# supply.net
KiCad netlist of a schematic drawn in EAGLE
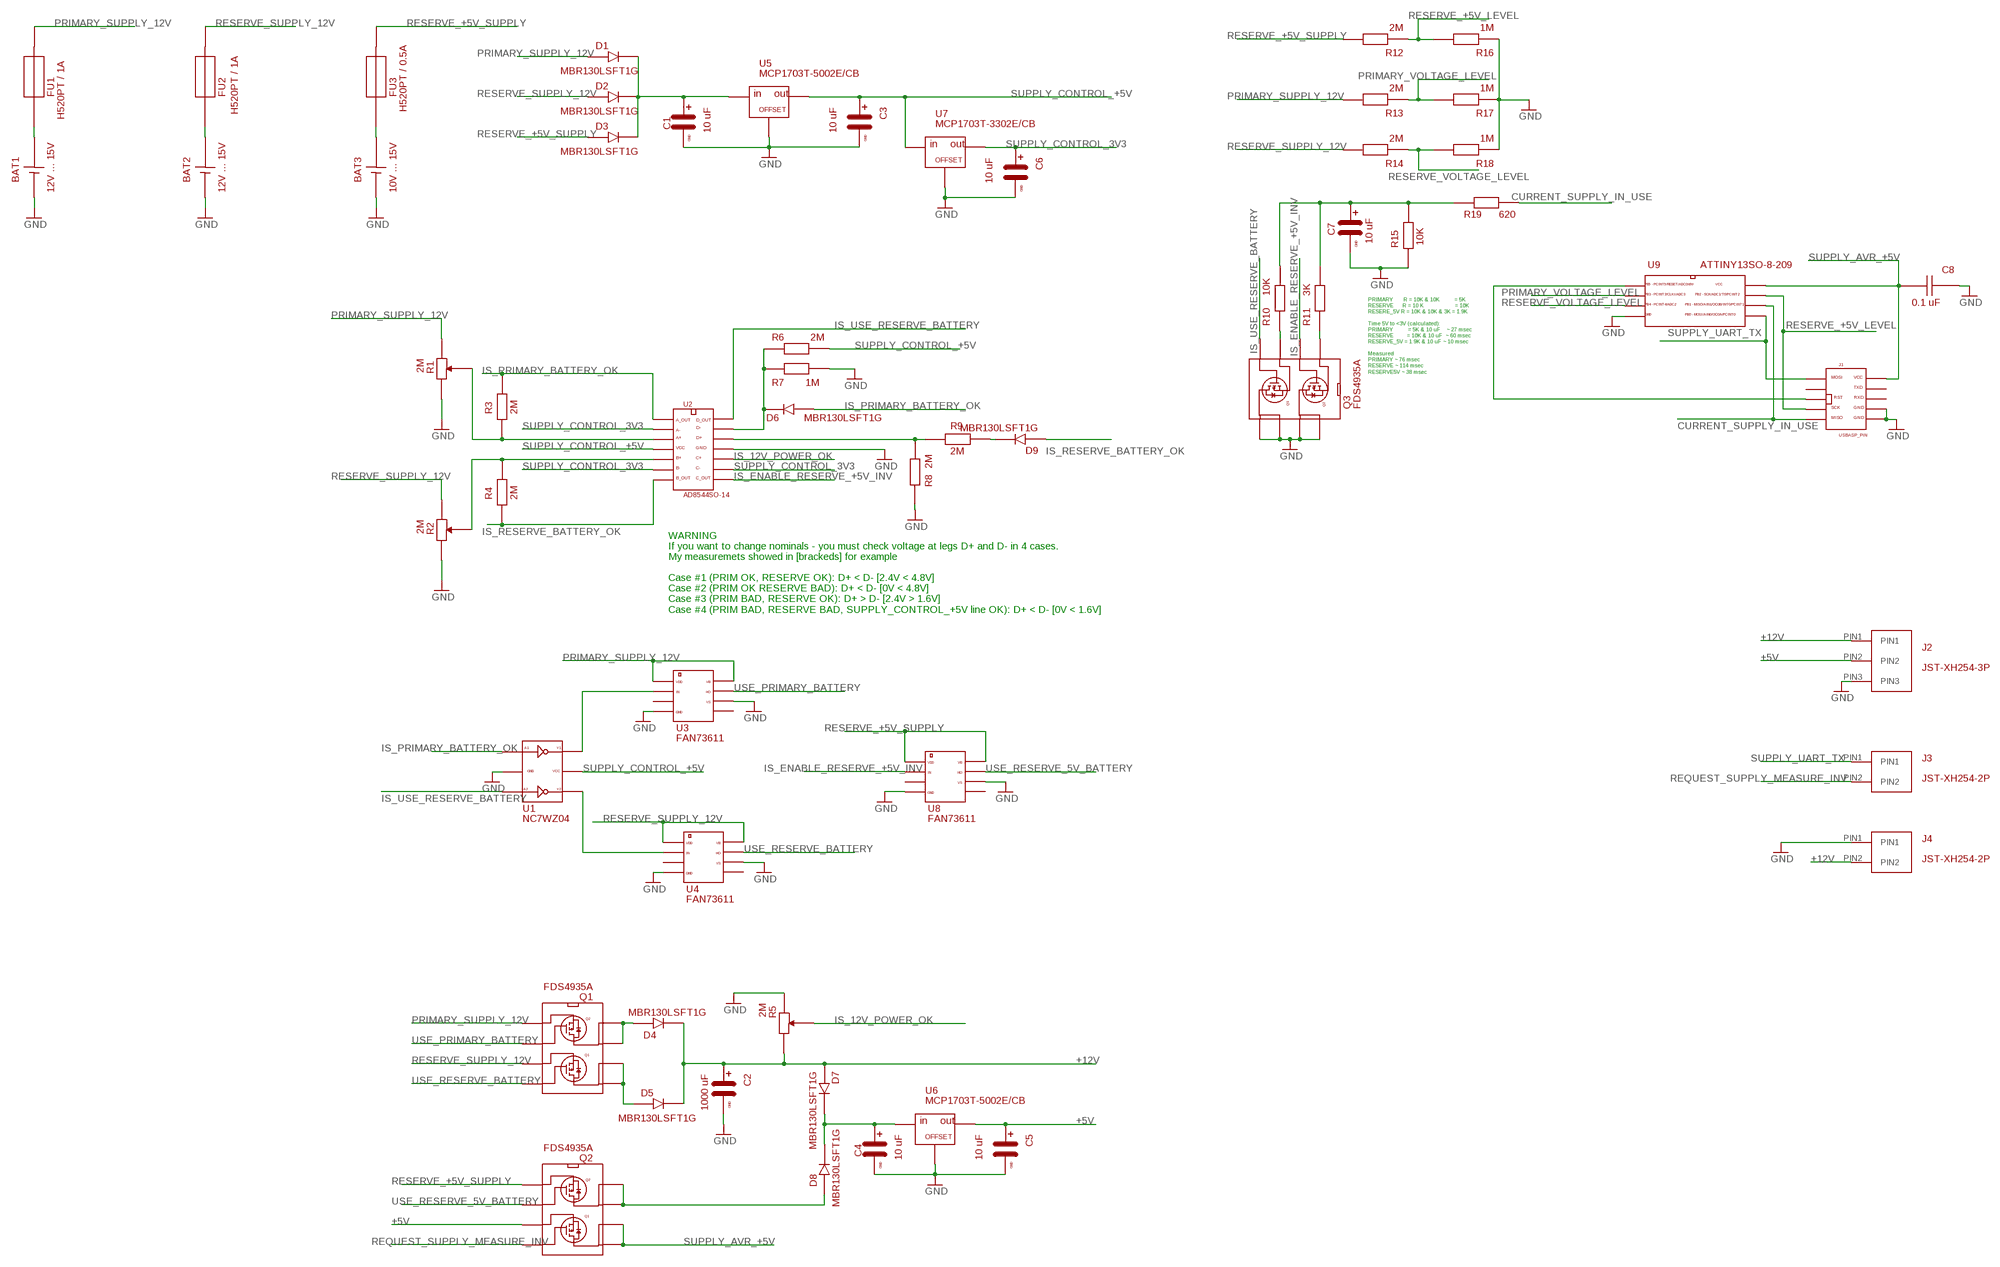
[diagram p0: schematic, sheet 1]

(export (version "E")
  (design (tool "Eeschema 10.0.6"))
  (components
    (comp (ref "BAT1")
      (value "12V ... 15V")
      (footprint "eagle-import:BATTERY")
      (libsource (lib "eagle-import") (part "BATTERY"))
    )
    (comp (ref "BAT2")
      (value "12V ... 15V")
      (footprint "eagle-import:BATTERY")
      (libsource (lib "eagle-import") (part "BATTERY"))
    )
    (comp (ref "BAT3")
      (value "10V ... 15V")
      (footprint "eagle-import:BATTERY")
      (libsource (lib "eagle-import") (part "BATTERY"))
    )
    (comp (ref "C1")
      (value "10 uF")
      (footprint "eagle-import:C-MINI-5X7")
      (libsource (lib "eagle-import") (part "CMINI-5X7"))
    )
    (comp (ref "C2")
      (value "1000 uF")
      (footprint "eagle-import:C")
      (libsource (lib "eagle-import") (part "C"))
    )
    (comp (ref "C3")
      (value "10 uF")
      (footprint "eagle-import:C-MINI-5X7")
      (libsource (lib "eagle-import") (part "CMINI-5X7"))
    )
    (comp (ref "C4")
      (value "10 uF")
      (footprint "eagle-import:C-MINI-5X7")
      (libsource (lib "eagle-import") (part "CMINI-5X7"))
    )
    (comp (ref "C5")
      (value "10 uF")
      (footprint "eagle-import:C-MINI-5X7")
      (libsource (lib "eagle-import") (part "CMINI-5X7"))
    )
    (comp (ref "C6")
      (value "10 uF")
      (footprint "eagle-import:C-MINI-5X7")
      (libsource (lib "eagle-import") (part "CMINI-5X7"))
    )
    (comp (ref "C7")
      (value "10 uF")
      (footprint "eagle-import:C-MINI-5X7")
      (libsource (lib "eagle-import") (part "CMINI-5X7"))
    )
    (comp (ref "C8")
      (value "0.1 uF")
      (footprint "eagle-import:C-1")
      (libsource (lib "eagle-import") (part "C-1"))
    )
    (comp (ref "D1")
      (value "MBR130LSFT1G")
      (footprint "eagle-import:D-SOD-123FL")
      (libsource (lib "eagle-import") (part "DSOD-123FL"))
    )
    (comp (ref "D2")
      (value "MBR130LSFT1G")
      (footprint "eagle-import:D-SOD-123FL")
      (libsource (lib "eagle-import") (part "DSOD-123FL"))
    )
    (comp (ref "D3")
      (value "MBR130LSFT1G")
      (footprint "eagle-import:D-SOD-123FL")
      (libsource (lib "eagle-import") (part "DSOD-123FL"))
    )
    (comp (ref "D4")
      (value "MBR130LSFT1G")
      (footprint "eagle-import:D-SOD-123FL")
      (libsource (lib "eagle-import") (part "DSOD-123FL"))
    )
    (comp (ref "D5")
      (value "MBR130LSFT1G")
      (footprint "eagle-import:D-SOD-123FL")
      (libsource (lib "eagle-import") (part "DSOD-123FL"))
    )
    (comp (ref "D6")
      (value "MBR130LSFT1G")
      (footprint "eagle-import:D-SOD-123FL")
      (libsource (lib "eagle-import") (part "DSOD-123FL"))
    )
    (comp (ref "D7")
      (value "MBR130LSFT1G")
      (footprint "eagle-import:D-SOD-123FL")
      (libsource (lib "eagle-import") (part "DSOD-123FL"))
    )
    (comp (ref "D8")
      (value "MBR130LSFT1G")
      (footprint "eagle-import:D-SOD-123FL")
      (libsource (lib "eagle-import") (part "DSOD-123FL"))
    )
    (comp (ref "D9")
      (value "MBR130LSFT1G")
      (footprint "eagle-import:D-SOD-123FL")
      (libsource (lib "eagle-import") (part "DSOD-123FL"))
    )
    (comp (ref "FU1")
      (value "H520PT / 1A")
      (footprint "eagle-import:FU")
      (libsource (lib "eagle-import") (part "FU"))
    )
    (comp (ref "FU2")
      (value "H520PT / 1A")
      (footprint "eagle-import:FU")
      (libsource (lib "eagle-import") (part "FU"))
    )
    (comp (ref "FU3")
      (value "H520PT / 0.5A")
      (footprint "eagle-import:FU")
      (libsource (lib "eagle-import") (part "FU"))
    )
    (comp (ref "J1")
      (value "USBASP_PIN")
      (footprint "eagle-import:USBASP_PIN")
      (libsource (lib "eagle-import") (part "USBASP_PIN"))
    )
    (comp (ref "J2")
      (value "JST-XH254-3P")
      (footprint "eagle-import:JST-XH254-3P")
      (libsource (lib "eagle-import") (part "JST-XH254-3P"))
    )
    (comp (ref "J3")
      (value "JST-XH254-2P")
      (footprint "eagle-import:JST-XH254-2P")
      (libsource (lib "eagle-import") (part "JST-XH254-2P"))
    )
    (comp (ref "J4")
      (value "JST-XH254-2P")
      (footprint "eagle-import:JST-XH254-2P")
      (libsource (lib "eagle-import") (part "JST-XH254-2P"))
    )
    (comp (ref "Q1")
      (value "FDS4935A")
      (footprint "eagle-import:SO-8")
      (libsource (lib "eagle-import") (part "MOSFET_P_X2"))
    )
    (comp (ref "Q2")
      (value "FDS4935A")
      (footprint "eagle-import:SO-8")
      (libsource (lib "eagle-import") (part "MOSFET_P_X2"))
    )
    (comp (ref "Q3")
      (value "FDS4935A")
      (footprint "eagle-import:SO-8")
      (libsource (lib "eagle-import") (part "MOSFET_P_X2"))
    )
    (comp (ref "R1")
      (value "2M")
      (footprint "eagle-import:RD-3296W-1-205LF")
      (libsource (lib "eagle-import") (part "RD3296W-1-205LF"))
    )
    (comp (ref "R2")
      (value "2M")
      (footprint "eagle-import:RD-3296W-1-205LF")
      (libsource (lib "eagle-import") (part "RD3296W-1-205LF"))
    )
    (comp (ref "R3") (value "2M") (footprint "eagle-import:R") (libsource (lib "eagle-import") (part "R")))
    (comp (ref "R4") (value "2M") (footprint "eagle-import:R") (libsource (lib "eagle-import") (part "R")))
    (comp (ref "R5")
      (value "2M")
      (footprint "eagle-import:RD-3296W-1-205LF")
      (libsource (lib "eagle-import") (part "RD3296W-1-205LF"))
    )
    (comp (ref "R6") (value "2M") (footprint "eagle-import:R") (libsource (lib "eagle-import") (part "R")))
    (comp (ref "R7") (value "1M") (footprint "eagle-import:R") (libsource (lib "eagle-import") (part "R")))
    (comp (ref "R8") (value "2M") (footprint "eagle-import:R") (libsource (lib "eagle-import") (part "R")))
    (comp (ref "R9") (value "2M") (footprint "eagle-import:R") (libsource (lib "eagle-import") (part "R")))
    (comp (ref "R10") (value "10K") (footprint "eagle-import:R") (libsource (lib "eagle-import") (part "R")))
    (comp (ref "R11") (value "3K") (footprint "eagle-import:R") (libsource (lib "eagle-import") (part "R")))
    (comp (ref "R12") (value "2M") (footprint "eagle-import:R") (libsource (lib "eagle-import") (part "R")))
    (comp (ref "R13") (value "2M") (footprint "eagle-import:R") (libsource (lib "eagle-import") (part "R")))
    (comp (ref "R14") (value "2M") (footprint "eagle-import:R") (libsource (lib "eagle-import") (part "R")))
    (comp (ref "R15") (value "10K") (footprint "eagle-import:R") (libsource (lib "eagle-import") (part "R")))
    (comp (ref "R16") (value "1M") (footprint "eagle-import:R") (libsource (lib "eagle-import") (part "R")))
    (comp (ref "R17") (value "1M") (footprint "eagle-import:R") (libsource (lib "eagle-import") (part "R")))
    (comp (ref "R18") (value "1M") (footprint "eagle-import:R") (libsource (lib "eagle-import") (part "R")))
    (comp (ref "R19") (value "620") (footprint "eagle-import:R") (libsource (lib "eagle-import") (part "R")))
    (comp (ref "U1")
      (value "NC7WZ04")
      (footprint "eagle-import:SC70")
      (libsource (lib "eagle-import") (part "INVERTER._X2"))
    )
    (comp (ref "U2")
      (value "AD8544SO-14")
      (footprint "eagle-import:SO-14")
      (libsource (lib "eagle-import") (part "AD8544SO-14"))
    )
    (comp (ref "U3")
      (value "FAN73611")
      (footprint "eagle-import:SOIC-8")
      (libsource (lib "eagle-import") (part "FAN73611"))
    )
    (comp (ref "U4")
      (value "FAN73611")
      (footprint "eagle-import:SOIC-8")
      (libsource (lib "eagle-import") (part "FAN73611"))
    )
    (comp (ref "U5")
      (value "MCP1703T-5002E/CB")
      (footprint "eagle-import:SOT-23A")
      (libsource (lib "eagle-import") (part "VOLTAGE_REGULATORSOT-23A"))
    )
    (comp (ref "U6")
      (value "MCP1703T-5002E/CB")
      (footprint "eagle-import:SOT-23A")
      (libsource (lib "eagle-import") (part "VOLTAGE_REGULATORSOT-23A"))
    )
    (comp (ref "U7")
      (value "MCP1703T-3302E/CB")
      (footprint "eagle-import:SOT-23A")
      (libsource (lib "eagle-import") (part "VOLTAGE_REGULATORSOT-23A"))
    )
    (comp (ref "U8")
      (value "FAN73611")
      (footprint "eagle-import:SOIC-8")
      (libsource (lib "eagle-import") (part "FAN73611"))
    )
    (comp (ref "U9")
      (value "ATTINY13SO-8-209")
      (footprint "eagle-import:SO-8-209")
      (libsource (lib "eagle-import") (part "ATTINY13SO-8-209"))
    )
  )
  (nets
    (net (code "1") (name "/+5V") (class "Default")
      (node (ref "C5") (pin "PLUS") (pinfunction "PIN_PLUS_PLUS") (pintype "bidirectional"))
      (node (ref "J2") (pin "PIN2") (pinfunction "PIN2_PIN2") (pintype "bidirectional"))
      (node (ref "Q2") (pin "P3") (pinfunction "S1_P3") (pintype "bidirectional"))
      (node (ref "U6") (pin "P2") (pinfunction "OUT_P2") (pintype "power_in"))
    )
    (net (code "2") (name "/+12V") (class "Default")
      (node (ref "C2") (pin "PIN_PLUS") (pinfunction "PIN_PLUS_PIN_PLUS") (pintype "bidirectional"))
      (node (ref "D4") (pin "CATHODE") (pinfunction "CATHODE_CATHODE") (pintype "bidirectional"))
      (node (ref "D5") (pin "CATHODE") (pinfunction "CATHODE_CATHODE") (pintype "bidirectional"))
      (node (ref "D7") (pin "ANODE") (pinfunction "ANODE_ANODE") (pintype "bidirectional"))
      (node (ref "J2") (pin "PIN1") (pinfunction "PIN1_PIN1") (pintype "bidirectional"))
      (node (ref "J4") (pin "PIN2") (pinfunction "PIN2_PIN2") (pintype "bidirectional"))
      (node (ref "R5") (pin "P2") (pinfunction "P2_P2") (pintype "bidirectional"))
    )
    (net (code "3") (name "/CURRENT_SUPPLY_IN_USE") (class "Default")
      (node (ref "J1") (pin "MISO") (pinfunction "MISO_MISO") (pintype "bidirectional"))
      (node (ref "R19") (pin "P$2") (pinfunction "P$2_P$2") (pintype "bidirectional"))
      (node (ref "U9") (pin "P6") (pinfunction "PB1_P6") (pintype "bidirectional"))
    )
    (net (code "4") (name "/IS_12V_POWER_OK") (class "Default")
      (node (ref "R5") (pin "P3") (pinfunction "P3_P3") (pintype "bidirectional"))
      (node (ref "U2") (pin "P10") (pinfunction "C+_P10") (pintype "bidirectional"))
    )
    (net (code "5") (name "/IS_ENABLE_RESERVE_+5V_INV") (class "Default")
      (node (ref "Q3") (pin "P2") (pinfunction "G2_P2") (pintype "bidirectional"))
      (node (ref "U2") (pin "P8") (pinfunction "C_OUT_P8") (pintype "bidirectional"))
      (node (ref "U8") (pin "P_2") (pinfunction "IN_P_2") (pintype "input"))
    )
    (net (code "6") (name "/IS_PRIMARY_BATTERY_OK") (class "Default")
      (node (ref "D6") (pin "ANODE") (pinfunction "ANODE_ANODE") (pintype "bidirectional"))
      (node (ref "R3") (pin "P$2") (pinfunction "P$2_P$2") (pintype "bidirectional"))
      (node (ref "U1") (pin "P1") (pinfunction "A1_P1") (pintype "bidirectional"))
      (node (ref "U2") (pin "P1") (pinfunction "A_OUT_P1") (pintype "bidirectional"))
    )
    (net (code "7") (name "/IS_RESERVE_BATTERY_OK") (class "Default")
      (node (ref "D9") (pin "ANODE") (pinfunction "ANODE_ANODE") (pintype "bidirectional"))
      (node (ref "R4") (pin "P$1") (pinfunction "P$1_P$1") (pintype "bidirectional"))
      (node (ref "U2") (pin "P7") (pinfunction "B_OUT_P7") (pintype "bidirectional"))
    )
    (net (code "8") (name "/IS_USE_RESERVE_BATTERY") (class "Default")
      (node (ref "Q3") (pin "P4") (pinfunction "G1_P4") (pintype "bidirectional"))
      (node (ref "U1") (pin "P3") (pinfunction "A2_P3") (pintype "bidirectional"))
      (node (ref "U2") (pin "P14") (pinfunction "D_OUT_P14") (pintype "bidirectional"))
    )
    (net (code "9") (name "/PRIMARY_SUPPLY_12V") (class "Default")
      (node (ref "D1") (pin "ANODE") (pinfunction "ANODE_ANODE") (pintype "bidirectional"))
      (node (ref "FU1") (pin "P$2") (pinfunction "P$2_P$2") (pintype "bidirectional"))
      (node (ref "Q1") (pin "P1") (pinfunction "S2_P1") (pintype "bidirectional"))
      (node (ref "R1") (pin "P1") (pinfunction "P1_P1") (pintype "bidirectional"))
      (node (ref "R13") (pin "P$2") (pinfunction "P$2_P$2") (pintype "bidirectional"))
      (node (ref "U3") (pin "P_1") (pinfunction "VDD_P_1") (pintype "power_in"))
      (node (ref "U3") (pin "P_8") (pinfunction "VB_P_8") (pintype "power_in"))
    )
    (net (code "10") (name "/PRIMARY_VOLTAGE_LEVEL") (class "Default")
      (node (ref "R13") (pin "P$1") (pinfunction "P$1_P$1") (pintype "bidirectional"))
      (node (ref "R17") (pin "P$2") (pinfunction "P$2_P$2") (pintype "bidirectional"))
      (node (ref "U9") (pin "P2") (pinfunction "PB3_P2") (pintype "bidirectional"))
    )
    (net (code "11") (name "/REQUEST_SUPPLY_MEASURE_INV") (class "Default")
      (node (ref "J3") (pin "PIN2") (pinfunction "PIN2_PIN2") (pintype "bidirectional"))
      (node (ref "Q2") (pin "P4") (pinfunction "G1_P4") (pintype "bidirectional"))
    )
    (net (code "12") (name "/RESERVE_+5V_LEVEL") (class "Default")
      (node (ref "J1") (pin "SCK") (pinfunction "SCK_SCK") (pintype "bidirectional"))
      (node (ref "R12") (pin "P$1") (pinfunction "P$1_P$1") (pintype "bidirectional"))
      (node (ref "R16") (pin "P$2") (pinfunction "P$2_P$2") (pintype "bidirectional"))
      (node (ref "U9") (pin "P7") (pinfunction "PB2_P7") (pintype "bidirectional"))
    )
    (net (code "13") (name "/RESERVE_+5V_SUPPLY") (class "Default")
      (node (ref "D3") (pin "ANODE") (pinfunction "ANODE_ANODE") (pintype "bidirectional"))
      (node (ref "FU3") (pin "P$2") (pinfunction "P$2_P$2") (pintype "bidirectional"))
      (node (ref "Q2") (pin "P1") (pinfunction "S2_P1") (pintype "bidirectional"))
      (node (ref "R12") (pin "P$2") (pinfunction "P$2_P$2") (pintype "bidirectional"))
      (node (ref "U8") (pin "P_1") (pinfunction "VDD_P_1") (pintype "power_in"))
      (node (ref "U8") (pin "P_8") (pinfunction "VB_P_8") (pintype "power_in"))
    )
    (net (code "14") (name "/RESERVE_SUPPLY_12V") (class "Default")
      (node (ref "D2") (pin "ANODE") (pinfunction "ANODE_ANODE") (pintype "bidirectional"))
      (node (ref "FU2") (pin "P$2") (pinfunction "P$2_P$2") (pintype "bidirectional"))
      (node (ref "Q1") (pin "P3") (pinfunction "S1_P3") (pintype "bidirectional"))
      (node (ref "R14") (pin "P$2") (pinfunction "P$2_P$2") (pintype "bidirectional"))
      (node (ref "R2") (pin "P1") (pinfunction "P1_P1") (pintype "bidirectional"))
      (node (ref "U4") (pin "P_1") (pinfunction "VDD_P_1") (pintype "power_in"))
      (node (ref "U4") (pin "P_8") (pinfunction "VB_P_8") (pintype "power_in"))
    )
    (net (code "15") (name "/RESERVE_VOLTAGE_LEVEL") (class "Default")
      (node (ref "R14") (pin "P$1") (pinfunction "P$1_P$1") (pintype "bidirectional"))
      (node (ref "R18") (pin "P$2") (pinfunction "P$2_P$2") (pintype "bidirectional"))
      (node (ref "U9") (pin "P3") (pinfunction "PB4_P3") (pintype "bidirectional"))
    )
    (net (code "16") (name "/SUPPLY_AVR_+5V") (class "Default")
      (node (ref "C8") (pin "P$1") (pinfunction "P$1_P$1") (pintype "bidirectional"))
      (node (ref "J1") (pin "VCC") (pinfunction "VCC_VCC") (pintype "power_in"))
      (node (ref "Q2") (pin "P5") (pinfunction "D11_P5") (pintype "bidirectional"))
      (node (ref "Q2") (pin "P6") (pinfunction "D12_P6") (pintype "bidirectional"))
      (node (ref "U9") (pin "P8") (pinfunction "VCC_P8") (pintype "power_in"))
    )
    (net (code "17") (name "/SUPPLY_CONTROL_+5V") (class "Default")
      (node (ref "C3") (pin "PLUS") (pinfunction "PIN_PLUS_PLUS") (pintype "bidirectional"))
      (node (ref "R6") (pin "P$1") (pinfunction "P$1_P$1") (pintype "bidirectional"))
      (node (ref "U1") (pin "P5") (pinfunction "VCC_P5") (pintype "power_in"))
      (node (ref "U2") (pin "P4") (pinfunction "VCC_P4") (pintype "power_in"))
      (node (ref "U5") (pin "P2") (pinfunction "OUT_P2") (pintype "power_in"))
      (node (ref "U7") (pin "P3") (pinfunction "IN_P3") (pintype "power_in"))
    )
    (net (code "18") (name "/SUPPLY_CONTROL_3V3") (class "Default")
      (node (ref "C6") (pin "PLUS") (pinfunction "PIN_PLUS_PLUS") (pintype "bidirectional"))
      (node (ref "U2") (pin "P2") (pinfunction "A-_P2") (pintype "bidirectional"))
      (node (ref "U2") (pin "P6") (pinfunction "B-_P6") (pintype "bidirectional"))
      (node (ref "U2") (pin "P9") (pinfunction "C-_P9") (pintype "bidirectional"))
      (node (ref "U7") (pin "P2") (pinfunction "OUT_P2") (pintype "power_in"))
    )
    (net (code "19") (name "/SUPPLY_UART_TX") (class "Default")
      (node (ref "J1") (pin "MOSI") (pinfunction "MOSI_MOSI") (pintype "bidirectional"))
      (node (ref "J3") (pin "PIN1") (pinfunction "PIN1_PIN1") (pintype "bidirectional"))
      (node (ref "U9") (pin "P5") (pinfunction "PB0_P5") (pintype "bidirectional"))
    )
    (net (code "20") (name "/USE_PRIMARY_BATTERY") (class "Default")
      (node (ref "Q1") (pin "P2") (pinfunction "G2_P2") (pintype "bidirectional"))
      (node (ref "U3") (pin "P_7") (pinfunction "HO_P_7") (pintype "output"))
    )
    (net (code "21") (name "/USE_RESERVE_5V_BATTERY") (class "Default")
      (node (ref "Q2") (pin "P2") (pinfunction "G2_P2") (pintype "bidirectional"))
      (node (ref "U8") (pin "P_7") (pinfunction "HO_P_7") (pintype "output"))
    )
    (net (code "22") (name "/USE_RESERVE_BATTERY") (class "Default")
      (node (ref "Q1") (pin "P4") (pinfunction "G1_P4") (pintype "bidirectional"))
      (node (ref "U4") (pin "P_7") (pinfunction "HO_P_7") (pintype "output"))
    )
    (net (code "23") (name "GND") (class "Default")
      (node (ref "BAT1") (pin "MINUS") (pinfunction "MINUS_MINUS") (pintype "power_in"))
      (node (ref "BAT2") (pin "MINUS") (pinfunction "MINUS_MINUS") (pintype "power_in"))
      (node (ref "BAT3") (pin "MINUS") (pinfunction "MINUS_MINUS") (pintype "power_in"))
      (node (ref "C1") (pin "MINUS") (pinfunction "PIN_GND_MINUS") (pintype "bidirectional"))
      (node (ref "C2") (pin "PIN_GND") (pinfunction "PIN_GND_PIN_GND") (pintype "bidirectional"))
      (node (ref "C3") (pin "MINUS") (pinfunction "PIN_GND_MINUS") (pintype "bidirectional"))
      (node (ref "C4") (pin "MINUS") (pinfunction "PIN_GND_MINUS") (pintype "bidirectional"))
      (node (ref "C5") (pin "MINUS") (pinfunction "PIN_GND_MINUS") (pintype "bidirectional"))
      (node (ref "C6") (pin "MINUS") (pinfunction "PIN_GND_MINUS") (pintype "bidirectional"))
      (node (ref "C7") (pin "MINUS") (pinfunction "PIN_GND_MINUS") (pintype "bidirectional"))
      (node (ref "C8") (pin "P$2") (pinfunction "P$2_P$2") (pintype "bidirectional"))
      (node (ref "J1") (pin "GND") (pinfunction "GND_GND") (pintype "power_in"))
      (node (ref "J1") (pin "GND1") (pinfunction "GND1_GND1") (pintype "power_in"))
      (node (ref "J2") (pin "PIN3") (pinfunction "PIN3_PIN3") (pintype "bidirectional"))
      (node (ref "J4") (pin "PIN1") (pinfunction "PIN1_PIN1") (pintype "bidirectional"))
      (node (ref "Q3") (pin "P5") (pinfunction "D11_P5") (pintype "bidirectional"))
      (node (ref "Q3") (pin "P6") (pinfunction "D12_P6") (pintype "bidirectional"))
      (node (ref "Q3") (pin "P7") (pinfunction "D21_P7") (pintype "bidirectional"))
      (node (ref "Q3") (pin "P8") (pinfunction "D22_P8") (pintype "bidirectional"))
      (node (ref "R1") (pin "P2") (pinfunction "P2_P2") (pintype "bidirectional"))
      (node (ref "R15") (pin "P$1") (pinfunction "P$1_P$1") (pintype "bidirectional"))
      (node (ref "R16") (pin "P$1") (pinfunction "P$1_P$1") (pintype "bidirectional"))
      (node (ref "R17") (pin "P$1") (pinfunction "P$1_P$1") (pintype "bidirectional"))
      (node (ref "R18") (pin "P$1") (pinfunction "P$1_P$1") (pintype "bidirectional"))
      (node (ref "R2") (pin "P2") (pinfunction "P2_P2") (pintype "bidirectional"))
      (node (ref "R5") (pin "P1") (pinfunction "P1_P1") (pintype "bidirectional"))
      (node (ref "R7") (pin "P$1") (pinfunction "P$1_P$1") (pintype "bidirectional"))
      (node (ref "R8") (pin "P$2") (pinfunction "P$2_P$2") (pintype "bidirectional"))
      (node (ref "U1") (pin "P2") (pinfunction "GND_P2") (pintype "power_in"))
      (node (ref "U2") (pin "P11") (pinfunction "GND_P11") (pintype "power_in"))
      (node (ref "U3") (pin "P_4") (pinfunction "GND_P_4") (pintype "power_in"))
      (node (ref "U3") (pin "P_6") (pinfunction "VS_P_6") (pintype "input"))
      (node (ref "U4") (pin "P_4") (pinfunction "GND_P_4") (pintype "power_in"))
      (node (ref "U4") (pin "P_6") (pinfunction "VS_P_6") (pintype "input"))
      (node (ref "U5") (pin "P1") (pinfunction "GND_P1") (pintype "power_in"))
      (node (ref "U6") (pin "P1") (pinfunction "GND_P1") (pintype "power_in"))
      (node (ref "U7") (pin "P1") (pinfunction "GND_P1") (pintype "power_in"))
      (node (ref "U8") (pin "P_4") (pinfunction "GND_P_4") (pintype "power_in"))
      (node (ref "U8") (pin "P_6") (pinfunction "VS_P_6") (pintype "input"))
      (node (ref "U9") (pin "P4") (pinfunction "GND_P4") (pintype "power_in"))
    )
    (net (code "24") (name "Net-(BAT1-PadPLUS)") (class "Default")
      (node (ref "BAT1") (pin "PLUS") (pinfunction "PLUS_PLUS") (pintype "power_in"))
      (node (ref "FU1") (pin "P$1") (pinfunction "P$1_P$1") (pintype "bidirectional"))
    )
    (net (code "25") (name "Net-(BAT2-PadPLUS)") (class "Default")
      (node (ref "BAT2") (pin "PLUS") (pinfunction "PLUS_PLUS") (pintype "power_in"))
      (node (ref "FU2") (pin "P$1") (pinfunction "P$1_P$1") (pintype "bidirectional"))
    )
    (net (code "26") (name "Net-(BAT3-PadPLUS)") (class "Default")
      (node (ref "BAT3") (pin "PLUS") (pinfunction "PLUS_PLUS") (pintype "power_in"))
      (node (ref "FU3") (pin "P$1") (pinfunction "P$1_P$1") (pintype "bidirectional"))
    )
    (net (code "27") (name "Net-(C1-PIN_PLUS)") (class "Default")
      (node (ref "C1") (pin "PLUS") (pinfunction "PIN_PLUS_PLUS") (pintype "bidirectional"))
      (node (ref "D1") (pin "CATHODE") (pinfunction "CATHODE_CATHODE") (pintype "bidirectional"))
      (node (ref "D2") (pin "CATHODE") (pinfunction "CATHODE_CATHODE") (pintype "bidirectional"))
      (node (ref "D3") (pin "CATHODE") (pinfunction "CATHODE_CATHODE") (pintype "bidirectional"))
      (node (ref "U5") (pin "P3") (pinfunction "IN_P3") (pintype "power_in"))
    )
    (net (code "28") (name "Net-(C4-PIN_PLUS)") (class "Default")
      (node (ref "C4") (pin "PLUS") (pinfunction "PIN_PLUS_PLUS") (pintype "bidirectional"))
      (node (ref "D7") (pin "CATHODE") (pinfunction "CATHODE_CATHODE") (pintype "bidirectional"))
      (node (ref "D8") (pin "CATHODE") (pinfunction "CATHODE_CATHODE") (pintype "bidirectional"))
      (node (ref "U6") (pin "P3") (pinfunction "IN_P3") (pintype "power_in"))
    )
    (net (code "29") (name "Net-(C7-PIN_PLUS)") (class "Default")
      (node (ref "C7") (pin "PLUS") (pinfunction "PIN_PLUS_PLUS") (pintype "bidirectional"))
      (node (ref "R10") (pin "P$2") (pinfunction "P$2_P$2") (pintype "bidirectional"))
      (node (ref "R11") (pin "P$2") (pinfunction "P$2_P$2") (pintype "bidirectional"))
      (node (ref "R15") (pin "P$2") (pinfunction "P$2_P$2") (pintype "bidirectional"))
      (node (ref "R19") (pin "P$1") (pinfunction "P$1_P$1") (pintype "bidirectional"))
    )
    (net (code "30") (name "Net-(D9-PadCATHODE)") (class "Default")
      (node (ref "D9") (pin "CATHODE") (pinfunction "CATHODE_CATHODE") (pintype "bidirectional"))
      (node (ref "R9") (pin "P$2") (pinfunction "P$2_P$2") (pintype "bidirectional"))
    )
    (net (code "31") (name "Net-(J1-RESET)") (class "Default")
      (node (ref "J1") (pin "RST") (pinfunction "RESET_RST") (pintype "bidirectional"))
      (node (ref "U9") (pin "P1") (pinfunction "PB5_P1") (pintype "bidirectional"))
    )
    (net (code "32") (name "Net-(Q1-D11)") (class "Default")
      (node (ref "D5") (pin "ANODE") (pinfunction "ANODE_ANODE") (pintype "bidirectional"))
      (node (ref "Q1") (pin "P5") (pinfunction "D11_P5") (pintype "bidirectional"))
      (node (ref "Q1") (pin "P6") (pinfunction "D12_P6") (pintype "bidirectional"))
    )
    (net (code "33") (name "Net-(Q1-D21)") (class "Default")
      (node (ref "D4") (pin "ANODE") (pinfunction "ANODE_ANODE") (pintype "bidirectional"))
      (node (ref "Q1") (pin "P7") (pinfunction "D21_P7") (pintype "bidirectional"))
      (node (ref "Q1") (pin "P8") (pinfunction "D22_P8") (pintype "bidirectional"))
    )
    (net (code "34") (name "Net-(Q2-D21)") (class "Default")
      (node (ref "D8") (pin "ANODE") (pinfunction "ANODE_ANODE") (pintype "bidirectional"))
      (node (ref "Q2") (pin "P7") (pinfunction "D21_P7") (pintype "bidirectional"))
      (node (ref "Q2") (pin "P8") (pinfunction "D22_P8") (pintype "bidirectional"))
    )
    (net (code "35") (name "Net-(Q3-S1)") (class "Default")
      (node (ref "Q3") (pin "P3") (pinfunction "S1_P3") (pintype "bidirectional"))
      (node (ref "R10") (pin "P$1") (pinfunction "P$1_P$1") (pintype "bidirectional"))
    )
    (net (code "36") (name "Net-(Q3-S2)") (class "Default")
      (node (ref "Q3") (pin "P1") (pinfunction "S2_P1") (pintype "bidirectional"))
      (node (ref "R11") (pin "P$1") (pinfunction "P$1_P$1") (pintype "bidirectional"))
    )
    (net (code "37") (name "Net-(U1-Y1)") (class "Default")
      (node (ref "U1") (pin "P6") (pinfunction "Y1_P6") (pintype "bidirectional"))
      (node (ref "U3") (pin "P_2") (pinfunction "IN_P_2") (pintype "input"))
    )
    (net (code "38") (name "Net-(U1-Y2)") (class "Default")
      (node (ref "U1") (pin "P4") (pinfunction "Y2_P4") (pintype "bidirectional"))
      (node (ref "U4") (pin "P_2") (pinfunction "IN_P_2") (pintype "input"))
    )
    (net (code "39") (name "Net-(U2-A+)") (class "Default")
      (node (ref "R1") (pin "P3") (pinfunction "P3_P3") (pintype "bidirectional"))
      (node (ref "R3") (pin "P$1") (pinfunction "P$1_P$1") (pintype "bidirectional"))
      (node (ref "U2") (pin "P3") (pinfunction "A+_P3") (pintype "bidirectional"))
    )
    (net (code "40") (name "Net-(U2-B+)") (class "Default")
      (node (ref "R2") (pin "P3") (pinfunction "P3_P3") (pintype "bidirectional"))
      (node (ref "R4") (pin "P$2") (pinfunction "P$2_P$2") (pintype "bidirectional"))
      (node (ref "U2") (pin "P5") (pinfunction "B+_P5") (pintype "bidirectional"))
    )
    (net (code "41") (name "Net-(U2-D+)") (class "Default")
      (node (ref "R8") (pin "P$1") (pinfunction "P$1_P$1") (pintype "bidirectional"))
      (node (ref "R9") (pin "P$1") (pinfunction "P$1_P$1") (pintype "bidirectional"))
      (node (ref "U2") (pin "P12") (pinfunction "D+_P12") (pintype "bidirectional"))
    )
    (net (code "42") (name "Net-(U2-D-)") (class "Default")
      (node (ref "D6") (pin "CATHODE") (pinfunction "CATHODE_CATHODE") (pintype "bidirectional"))
      (node (ref "R6") (pin "P$2") (pinfunction "P$2_P$2") (pintype "bidirectional"))
      (node (ref "R7") (pin "P$2") (pinfunction "P$2_P$2") (pintype "bidirectional"))
      (node (ref "U2") (pin "P13") (pinfunction "D-_P13") (pintype "bidirectional"))
    )
    (net (code "43") (name "unconnected-(J1-PadNC1)") (class "Default")
      (node (ref "J1") (pin "NC1") (pinfunction "NC1_NC1") (pintype "no_connect"))
    )
    (net (code "44") (name "unconnected-(J1-PadRXD)") (class "Default")
      (node (ref "J1") (pin "RXD") (pinfunction "RXD_RXD") (pintype "bidirectional"))
    )
    (net (code "45") (name "unconnected-(J1-PadTXD)") (class "Default")
      (node (ref "J1") (pin "TXD") (pinfunction "TXD_TXD") (pintype "bidirectional"))
    )
    (net (code "46") (name "unconnected-(U3-NC1-PadP_3)") (class "Default")
      (node (ref "U3") (pin "P_3") (pinfunction "NC1_P_3") (pintype "no_connect"))
    )
    (net (code "47") (name "unconnected-(U3-NC2-PadP_5)") (class "Default")
      (node (ref "U3") (pin "P_5") (pinfunction "NC2_P_5") (pintype "no_connect"))
    )
    (net (code "48") (name "unconnected-(U4-NC1-PadP_3)") (class "Default")
      (node (ref "U4") (pin "P_3") (pinfunction "NC1_P_3") (pintype "no_connect"))
    )
    (net (code "49") (name "unconnected-(U4-NC2-PadP_5)") (class "Default")
      (node (ref "U4") (pin "P_5") (pinfunction "NC2_P_5") (pintype "no_connect"))
    )
    (net (code "50") (name "unconnected-(U8-NC1-PadP_3)") (class "Default")
      (node (ref "U8") (pin "P_3") (pinfunction "NC1_P_3") (pintype "no_connect"))
    )
    (net (code "51") (name "unconnected-(U8-NC2-PadP_5)") (class "Default")
      (node (ref "U8") (pin "P_5") (pinfunction "NC2_P_5") (pintype "no_connect"))
    )
  )
)
